# PWR_SUPPLY.net
KiCad netlist of a schematic drawn in Altium Designer
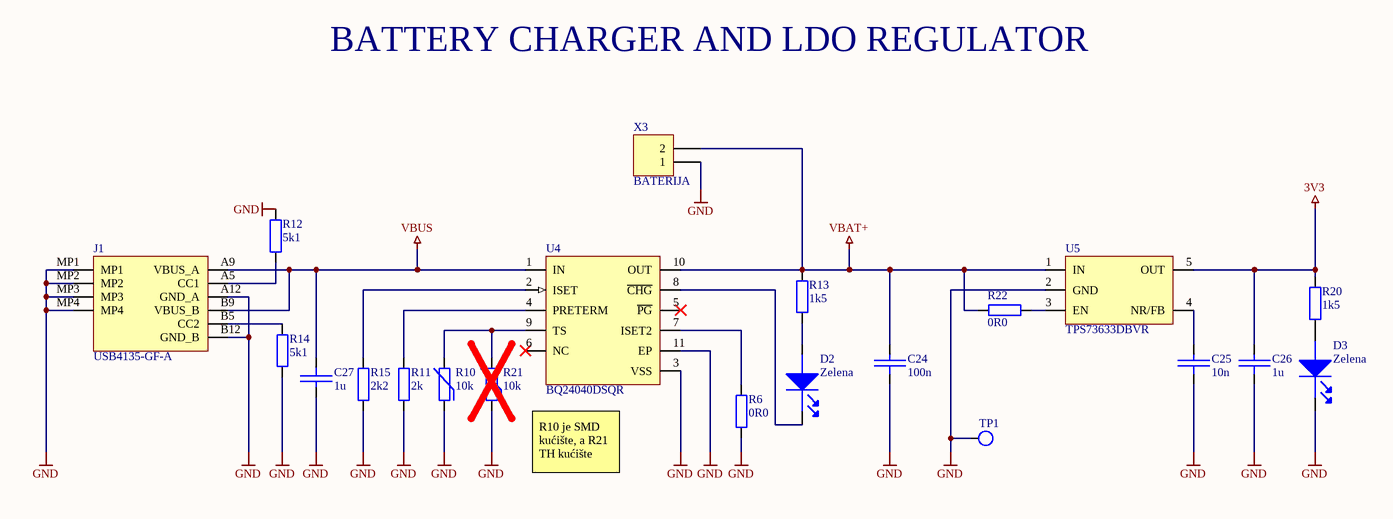
[diagram p0: PWR_SUPPLY.SchDoc]

(export (version "E")
  (design (tool "Eeschema 10.0.6"))
  (components
    (comp (ref "C24")
      (value "100n")
      (footprint "0805")
      (description "Kondenzator, X7R, 10%, 50VDC")
      (fields
        (field (name "MANUFACTURER") "TDK")
        (field (name "MANUFACTURER PART NUMBER") "C2012X7R1H104K125AE")
      )
      (libsource (lib "DZ1_Bruncic_Vito") (part "MCJCU21GBB7104KTPA01"))
    )
    (comp (ref "C25")
      (value "10n")
      (footprint "0805")
      (description "Kondenzator, C0G, 10%, 50VDC")
      (fields
        (field (name "MANUFACTURER") "KEMET")
        (field (name "MANUFACTURER PART NUMBER") "C0805C103K5RECAUTO")
      )
      (libsource (lib "DZ1_Bruncic_Vito") (part "C0805C103K5RECAUTO"))
    )
    (comp (ref "C26")
      (value "1u")
      (footprint "0603")
      (description "Kondenzator, X7R, 10%, 50VDC")
      (fields
        (field (name "MANUFACTURER") "TDK")
        (field (name "MANUFACTURER PART NUMBER") "C1608X7R1H105K080AB")
      )
      (libsource (lib "DZ1_Bruncic_Vito") (part "C1608X7R1H105K080AB"))
    )
    (comp (ref "C27")
      (value "1u")
      (footprint "0603")
      (description "Kondenzator, X7R, 10%, 50VDC")
      (fields
        (field (name "MANUFACTURER") "TDK")
        (field (name "MANUFACTURER PART NUMBER") "C1608X7R1H105K080AB")
      )
      (libsource (lib "DZ1_Bruncic_Vito") (part "C1608X7R1H105K080AB"))
    )
    (comp (ref "D2")
      (value "Zelena")
      (footprint "0805")
      (description "Dioda, svjetleća, 1,9V")
      (fields (field (name "MANUFACTURER") "Bivar") (field (name "MANUFACTURER PART NUMBER") "SM0805GCL"))
      (libsource (lib "DZ1_Bruncic_Vito") (part "SM0805GCL"))
    )
    (comp (ref "D3")
      (value "Zelena")
      (footprint "0805")
      (description "Dioda, svjetleća, 1,9V")
      (fields (field (name "MANUFACTURER") "Bivar") (field (name "MANUFACTURER PART NUMBER") "SM0805GCL"))
      (libsource (lib "DZ1_Bruncic_Vito") (part "SM0805GCL"))
    )
    (comp (ref "J1")
      (value "USB4135-GF-A")
      (footprint "USB4135GFA")
      (description "USB-C priključak")
      (fields (field (name "MOUSER PART NUMBER") "640-USB4135-GF-A"))
      (libsource (lib "DZ1_Bruncic_Vito") (part "USB4135-GF-A"))
    )
    (comp (ref "R6")
      (value "0R0")
      (footprint "0603")
      (description "Otpornik, 1%, 100mW")
      (libsource (lib "DZ1_Bruncic_Vito") (part "CRCW06030000Z0EA"))
    )
    (comp (ref "R10")
      (value "10k")
      (footprint "0402")
      (description "NTC Termistor, 1%")
      (libsource (lib "DZ1_Bruncic_Vito") (part "NTCG103JF103FT1"))
    )
    (comp (ref "R11")
      (value "2k")
      (footprint "0805")
      (description "Otpornik, 1%, 125mW")
      (fields
        (field (name "MANUFACTURER") "Yageo")
        (field (name "MANUFACTURER PART NUMBER") "RC0805FR-102KL")
      )
      (libsource (lib "DZ1_Bruncic_Vito") (part "RC0805FR-102KL"))
    )
    (comp (ref "R12")
      (value "5k1")
      (footprint "0603")
      (description "Otpornik, ±100ppm/C, 100mW")
      (fields
        (field (name "MANUFACTURER") "Yageo Group")
        (field (name "MANUFACTURER PART NUMBER") "AC0603FR-075K1L")
      )
      (libsource (lib "DZ1_Bruncic_Vito") (part "MCT06030C5101FPW00"))
    )
    (comp (ref "R13")
      (value "1k5")
      (footprint "0805")
      (description "Otpornik, ±50ppm/C, 100mW")
      (libsource (lib "DZ1_Bruncic_Vito") (part "MCU08050C1501FP5"))
    )
    (comp (ref "R14")
      (value "5k1")
      (footprint "0603")
      (description "Otpornik, ±100ppm/C, 100mW")
      (fields
        (field (name "MANUFACTURER") "Yageo Group")
        (field (name "MANUFACTURER PART NUMBER") "AC0603FR-075K1L")
      )
      (libsource (lib "DZ1_Bruncic_Vito") (part "MCT06030C5101FPW00"))
    )
    (comp (ref "R15")
      (value "2k2")
      (footprint "0805")
      (description "Otpornik, ±100ppm/C, 125mW")
      (fields
        (field (name "MANUFACTURER") "Panasonic")
        (field (name "MANUFACTURER PART NUMBER") "ERJ-PB6B2201V")
      )
      (libsource (lib "DZ1_Bruncic_Vito") (part "MCU08050C2201FP5"))
    )
    (comp (ref "R20")
      (value "1k5")
      (footprint "0805")
      (description "Otpornik, ±50ppm/C, 100mW")
      (libsource (lib "DZ1_Bruncic_Vito") (part "MCU08050C1501FP5"))
    )
    (comp (ref "R21")
      (value "10k")
      (footprint "TH NTC")
      (description "NTC Termistor, 1%")
      (libsource (lib "DZ1_Bruncic_Vito") (part "954-103AT-2"))
    )
    (comp (ref "R22")
      (value "0R0")
      (footprint "0603")
      (description "Otpornik, 1%, 100mW")
      (libsource (lib "DZ1_Bruncic_Vito") (part "CRCW06030000Z0EA"))
    )
    (comp (ref "TP1")
      (value "TEST_POINT")
      (footprint "TST_POINT")
      (libsource (lib "DZ1_Bruncic_Vito") (part "TEST_POINT"))
    )
    (comp (ref "U4")
      (value "BQ24040DSQR")
      (footprint "WSON-10")
      (description "Li-Ion baterija, 800mA")
      (fields (field (name "MOUSER PART NUMBER") "595-BQ24040DSQR"))
      (libsource (lib "DZ1_Bruncic_Vito") (part "BQ24040DSQR"))
    )
    (comp (ref "U5")
      (value "TPS73633DBVR")
      (footprint "SOT23 5pin")
      (description "IC Regulator, 3,3V, 400mADC")
      (fields (field (name "MANUFACTURER") "Texas Instruments"))
      (libsource (lib "DZ1_Bruncic_Vito") (part "TPS73633DBVR"))
    )
    (comp (ref "X3")
      (value "BATERIJA")
      (footprint "BATTERY")
      (description "Header, 2-Pin")
      (fields (field (name "PUBLISHER") "Altium Limited"))
      (libsource (lib "Miscellaneous Connectors") (part "Header 2"))
    )
  )
  (nets
    (net (code "1") (name "3V3") (class "Default")
      (node (ref "C26") (pin "2") (pinfunction "2_2") (pintype "passive"))
      (node (ref "R20") (pin "2") (pinfunction "2_2") (pintype "passive"))
      (node (ref "U5") (pin "5") (pinfunction "OUT_5") (pintype "passive"))
    )
    (net (code "2") (name "GND") (class "Default")
      (node (ref "C24") (pin "1") (pinfunction "1_1") (pintype "passive"))
      (node (ref "C25") (pin "1") (pinfunction "1_1") (pintype "passive"))
      (node (ref "C26") (pin "1") (pinfunction "1_1") (pintype "passive"))
      (node (ref "C27") (pin "2") (pinfunction "2_2") (pintype "passive"))
      (node (ref "D3") (pin "1") (pinfunction "Cathode_1") (pintype "passive"))
      (node (ref "J1") (pin "A12") (pinfunction "GND_A_A12") (pintype "passive"))
      (node (ref "J1") (pin "B12") (pinfunction "GND_B_B12") (pintype "passive"))
      (node (ref "J1") (pin "MP1") (pinfunction "MP1_MP1") (pintype "passive"))
      (node (ref "J1") (pin "MP2") (pinfunction "MP2_MP2") (pintype "passive"))
      (node (ref "J1") (pin "MP3") (pinfunction "MP3_MP3") (pintype "passive"))
      (node (ref "J1") (pin "MP4") (pinfunction "MP4_MP4") (pintype "passive"))
      (node (ref "R10") (pin "1") (pinfunction "1_1") (pintype "passive"))
      (node (ref "R11") (pin "1") (pinfunction "1_1") (pintype "passive"))
      (node (ref "R12") (pin "2") (pinfunction "2_2") (pintype "passive"))
      (node (ref "R14") (pin "1") (pinfunction "1_1") (pintype "passive"))
      (node (ref "R15") (pin "1") (pinfunction "1_1") (pintype "passive"))
      (node (ref "R21") (pin "1") (pinfunction "1_1") (pintype "passive"))
      (node (ref "R6") (pin "1") (pinfunction "1_1") (pintype "passive"))
      (node (ref "TP1") (pin "1") (pinfunction "1_1") (pintype "passive"))
      (node (ref "U4") (pin "11") (pinfunction "EP_11") (pintype "passive"))
      (node (ref "U4") (pin "3") (pinfunction "VSS_3") (pintype "power_in"))
      (node (ref "U5") (pin "2") (pinfunction "GND_2") (pintype "passive"))
      (node (ref "X3") (pin "1") (pinfunction "1_1") (pintype "passive"))
    )
    (net (code "3") (name "Net-(D2-Anode)") (class "Default")
      (node (ref "D2") (pin "2") (pinfunction "Anode_2") (pintype "passive"))
      (node (ref "R13") (pin "2") (pinfunction "2_2") (pintype "passive"))
    )
    (net (code "4") (name "Net-(D2-Cathode)") (class "Default")
      (node (ref "D2") (pin "1") (pinfunction "Cathode_1") (pintype "passive"))
      (node (ref "U4") (pin "8") (pinfunction "~{CHG}_8") (pintype "passive"))
    )
    (net (code "5") (name "Net-(D3-Anode)") (class "Default")
      (node (ref "D3") (pin "2") (pinfunction "Anode_2") (pintype "passive"))
      (node (ref "R20") (pin "1") (pinfunction "1_1") (pintype "passive"))
    )
    (net (code "6") (name "Net-(J1-CC1)") (class "Default")
      (node (ref "J1") (pin "A5") (pinfunction "CC1_A5") (pintype "passive"))
      (node (ref "R12") (pin "1") (pinfunction "1_1") (pintype "passive"))
    )
    (net (code "7") (name "Net-(J1-CC2)") (class "Default")
      (node (ref "J1") (pin "B5") (pinfunction "CC2_B5") (pintype "passive"))
      (node (ref "R14") (pin "2") (pinfunction "2_2") (pintype "passive"))
    )
    (net (code "8") (name "Net-(U4-ISET)") (class "Default")
      (node (ref "R15") (pin "2") (pinfunction "2_2") (pintype "passive"))
      (node (ref "U4") (pin "2") (pinfunction "ISET_2") (pintype "input"))
    )
    (net (code "9") (name "Net-(U4-ISET2)") (class "Default")
      (node (ref "R6") (pin "2") (pinfunction "2_2") (pintype "passive"))
      (node (ref "U4") (pin "7") (pinfunction "ISET2_7") (pintype "passive"))
    )
    (net (code "10") (name "Net-(U4-PRETERM)") (class "Default")
      (node (ref "R11") (pin "2") (pinfunction "2_2") (pintype "passive"))
      (node (ref "U4") (pin "4") (pinfunction "PRETERM_4") (pintype "passive"))
    )
    (net (code "11") (name "Net-(U4-TS)") (class "Default")
      (node (ref "R10") (pin "2") (pinfunction "2_2") (pintype "passive"))
      (node (ref "R21") (pin "2") (pinfunction "2_2") (pintype "passive"))
      (node (ref "U4") (pin "9") (pinfunction "TS_9") (pintype "passive"))
    )
    (net (code "12") (name "Net-(U5-EN)") (class "Default")
      (node (ref "R22") (pin "1") (pinfunction "1_1") (pintype "passive"))
      (node (ref "U5") (pin "3") (pinfunction "EN_3") (pintype "passive"))
    )
    (net (code "13") (name "Net-(U5-NR{slash}FB)") (class "Default")
      (node (ref "C25") (pin "2") (pinfunction "2_2") (pintype "passive"))
      (node (ref "U5") (pin "4") (pinfunction "NR/FB_4") (pintype "passive"))
    )
    (net (code "14") (name "VBAT+") (class "Default")
      (node (ref "C24") (pin "2") (pinfunction "2_2") (pintype "passive"))
      (node (ref "R13") (pin "1") (pinfunction "1_1") (pintype "passive"))
      (node (ref "R22") (pin "2") (pinfunction "2_2") (pintype "passive"))
      (node (ref "U4") (pin "10") (pinfunction "OUT_10") (pintype "power_in"))
      (node (ref "U5") (pin "1") (pinfunction "IN_1") (pintype "passive"))
      (node (ref "X3") (pin "2") (pinfunction "2_2") (pintype "passive"))
    )
    (net (code "15") (name "VBUS") (class "Default")
      (node (ref "C27") (pin "1") (pinfunction "1_1") (pintype "passive"))
      (node (ref "J1") (pin "A9") (pinfunction "VBUS_A_A9") (pintype "passive"))
      (node (ref "J1") (pin "B9") (pinfunction "VBUS_B_B9") (pintype "passive"))
      (node (ref "U4") (pin "1") (pinfunction "IN_1") (pintype "power_in"))
    )
    (net (code "16") (name "unconnected-(U4-NC-Pad6)") (class "Default")
      (node (ref "U4") (pin "6") (pinfunction "NC_6") (pintype "passive+no_connect"))
    )
    (net (code "17") (name "unconnected-(U4-~{PG}-Pad5)") (class "Default")
      (node (ref "U4") (pin "5") (pinfunction "~{PG}_5") (pintype "passive+no_connect"))
    )
  )
)
